# 13_FLOW_Sensor.net
KiCad netlist of a schematic drawn in Altium Designer
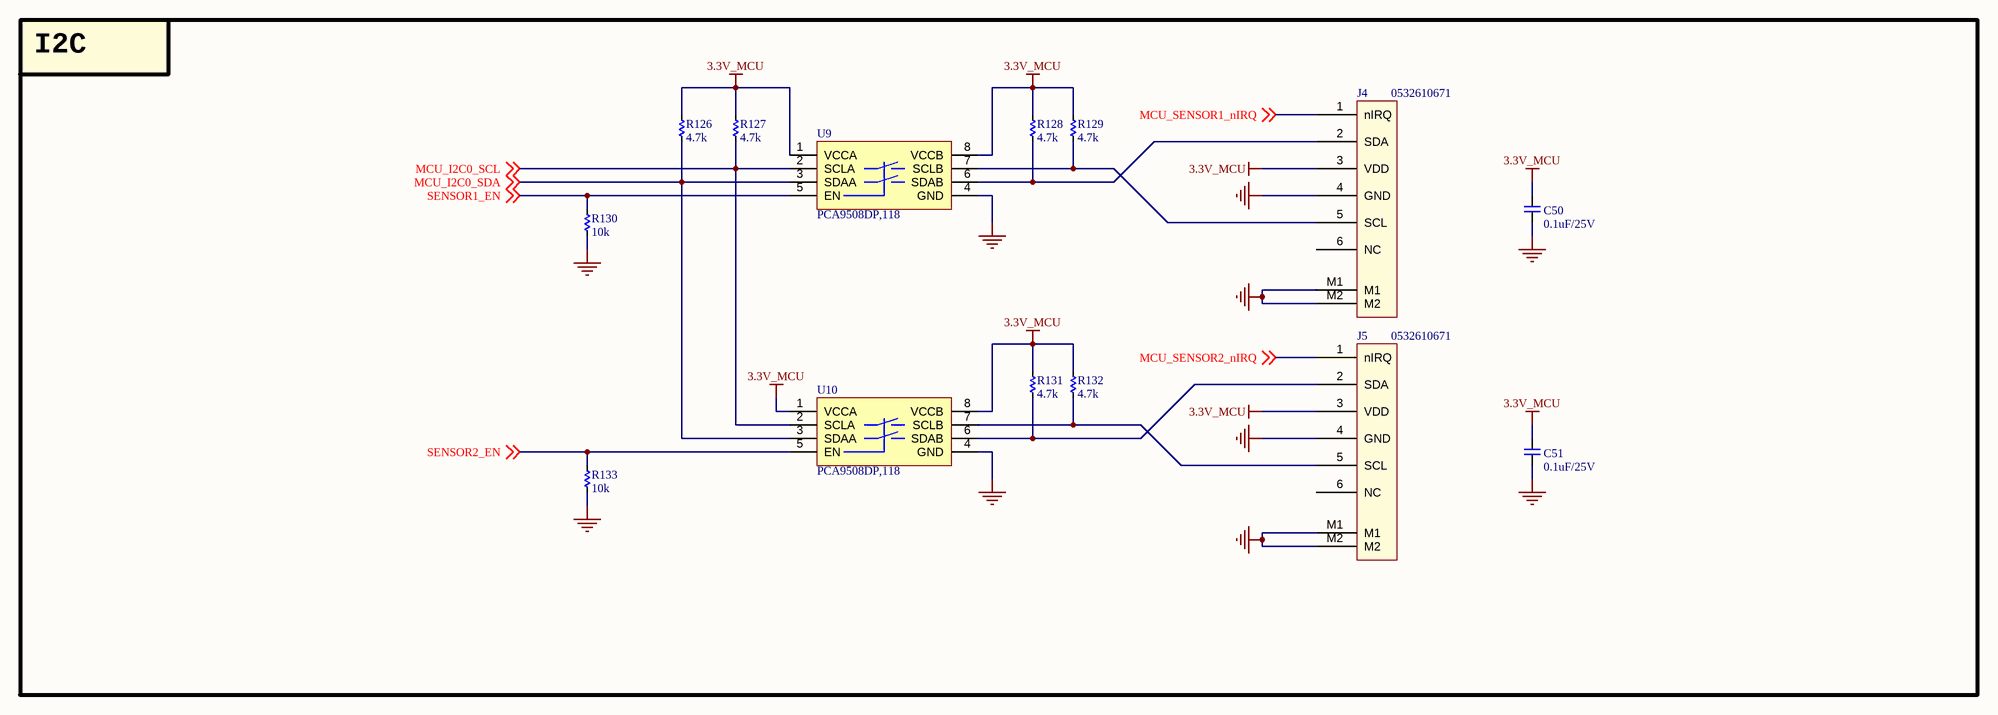
[diagram p0: 13_FLOW_Sensor.SchDoc]

(export (version "E")
  (design (tool "Eeschema 10.0.6"))
  (components
    (comp (ref "C50")
      (value "0.1uF/25V")
      (footprint "CAP_C_1005X60")
      (description "CAP")
      (libsource (lib "LABLIB") (part "_CAP_C_2"))
    )
    (comp (ref "C51")
      (value "0.1uF/25V")
      (footprint "CAP_C_1005X60")
      (description "CAP")
      (libsource (lib "LABLIB") (part "_CAP_C_2"))
    )
    (comp (ref "J4")
      (value "0532610671")
      (footprint "MOLEX_0532610671")
      (libsource (lib "LABLIB") (part "FLOW_SENSOR"))
    )
    (comp (ref "J5")
      (value "0532610671")
      (footprint "MOLEX_0532610671")
      (libsource (lib "LABLIB") (part "FLOW_SENSOR"))
    )
    (comp (ref "R126")
      (value "4.7k")
      (footprint "RES_C_1005X40")
      (description "RES")
      (libsource (lib "LABLIB") (part "_RES_B_2"))
    )
    (comp (ref "R127")
      (value "4.7k")
      (footprint "RES_C_1005X40")
      (description "RES")
      (libsource (lib "LABLIB") (part "_RES_B_2"))
    )
    (comp (ref "R128")
      (value "4.7k")
      (footprint "RES_C_1005X40")
      (description "RES")
      (libsource (lib "LABLIB") (part "_RES_B_2"))
    )
    (comp (ref "R129")
      (value "4.7k")
      (footprint "RES_C_1005X40")
      (description "RES")
      (libsource (lib "LABLIB") (part "_RES_B_2"))
    )
    (comp (ref "R130")
      (value "10k")
      (footprint "RES_C_1005X40")
      (description "RES")
      (libsource (lib "LABLIB") (part "_RES_B_2"))
    )
    (comp (ref "R131")
      (value "4.7k")
      (footprint "RES_C_1005X40")
      (description "RES")
      (libsource (lib "LABLIB") (part "_RES_B_2"))
    )
    (comp (ref "R132")
      (value "4.7k")
      (footprint "RES_C_1005X40")
      (description "RES")
      (libsource (lib "LABLIB") (part "_RES_B_2"))
    )
    (comp (ref "R133")
      (value "10k")
      (footprint "RES_C_1005X40")
      (description "RES")
      (libsource (lib "LABLIB") (part "_RES_B_2"))
    )
    (comp (ref "U9")
      (value "PCA9508DP,118")
      (footprint "TSOP8")
      (libsource (lib "BEE-DAL_EXP_sche") (part "PCA9508DP,118"))
    )
    (comp (ref "U10")
      (value "PCA9508DP,118")
      (footprint "TSOP8")
      (libsource (lib "BEE-DAL_EXP_sche") (part "PCA9508DP,118"))
    )
  )
  (nets
    (net (code "1") (name "3.3V_MCU") (class "Default")
      (node (ref "C50") (pin "2") (pinfunction "2_2") (pintype "passive"))
      (node (ref "C51") (pin "2") (pinfunction "2_2") (pintype "passive"))
      (node (ref "J4") (pin "3") (pinfunction "VDD_3") (pintype "passive"))
      (node (ref "J5") (pin "3") (pinfunction "VDD_3") (pintype "passive"))
      (node (ref "R126") (pin "1") (pinfunction "1_1") (pintype "passive"))
      (node (ref "R127") (pin "1") (pinfunction "1_1") (pintype "passive"))
      (node (ref "R128") (pin "1") (pinfunction "1_1") (pintype "passive"))
      (node (ref "R129") (pin "1") (pinfunction "1_1") (pintype "passive"))
      (node (ref "R131") (pin "1") (pinfunction "1_1") (pintype "passive"))
      (node (ref "R132") (pin "1") (pinfunction "1_1") (pintype "passive"))
      (node (ref "U10") (pin "1") (pinfunction "VCCA_1") (pintype "passive"))
      (node (ref "U10") (pin "8") (pinfunction "VCCB_8") (pintype "passive"))
      (node (ref "U9") (pin "1") (pinfunction "VCCA_1") (pintype "passive"))
      (node (ref "U9") (pin "8") (pinfunction "VCCB_8") (pintype "passive"))
    )
    (net (code "2") (name "GND") (class "Default")
      (node (ref "C50") (pin "1") (pinfunction "1_1") (pintype "passive"))
      (node (ref "C51") (pin "1") (pinfunction "1_1") (pintype "passive"))
      (node (ref "J4") (pin "4") (pinfunction "GND_4") (pintype "passive"))
      (node (ref "J4") (pin "M1") (pinfunction "M1_M1") (pintype "passive"))
      (node (ref "J4") (pin "M2") (pinfunction "M2_M2") (pintype "passive"))
      (node (ref "J5") (pin "4") (pinfunction "GND_4") (pintype "passive"))
      (node (ref "J5") (pin "M1") (pinfunction "M1_M1") (pintype "passive"))
      (node (ref "J5") (pin "M2") (pinfunction "M2_M2") (pintype "passive"))
      (node (ref "R130") (pin "2") (pinfunction "2_2") (pintype "passive"))
      (node (ref "R133") (pin "2") (pinfunction "2_2") (pintype "passive"))
      (node (ref "U10") (pin "4") (pinfunction "GND_4") (pintype "passive"))
      (node (ref "U9") (pin "4") (pinfunction "GND_4") (pintype "passive"))
    )
    (net (code "3") (name "MCU_I2C0_SCL") (class "Default")
      (node (ref "R127") (pin "2") (pinfunction "2_2") (pintype "passive"))
      (node (ref "U10") (pin "2") (pinfunction "SCLA_2") (pintype "passive"))
      (node (ref "U9") (pin "2") (pinfunction "SCLA_2") (pintype "passive"))
    )
    (net (code "4") (name "MCU_I2C0_SDA") (class "Default")
      (node (ref "R126") (pin "2") (pinfunction "2_2") (pintype "passive"))
      (node (ref "U10") (pin "3") (pinfunction "SDAA_3") (pintype "passive"))
      (node (ref "U9") (pin "3") (pinfunction "SDAA_3") (pintype "passive"))
    )
    (net (code "5") (name "MCU_SENSOR1_nIRQ") (class "Default")
      (node (ref "J4") (pin "1") (pinfunction "nIRQ_1") (pintype "passive"))
    )
    (net (code "6") (name "MCU_SENSOR2_nIRQ") (class "Default")
      (node (ref "J5") (pin "1") (pinfunction "nIRQ_1") (pintype "passive"))
    )
    (net (code "7") (name "Net-(J4-SCL)") (class "Default")
      (node (ref "J4") (pin "5") (pinfunction "SCL_5") (pintype "passive"))
      (node (ref "R129") (pin "2") (pinfunction "2_2") (pintype "passive"))
      (node (ref "U9") (pin "7") (pinfunction "SCLB_7") (pintype "passive"))
    )
    (net (code "8") (name "Net-(J4-SDA)") (class "Default")
      (node (ref "J4") (pin "2") (pinfunction "SDA_2") (pintype "passive"))
      (node (ref "R128") (pin "2") (pinfunction "2_2") (pintype "passive"))
      (node (ref "U9") (pin "6") (pinfunction "SDAB_6") (pintype "passive"))
    )
    (net (code "9") (name "Net-(J5-SCL)") (class "Default")
      (node (ref "J5") (pin "5") (pinfunction "SCL_5") (pintype "passive"))
      (node (ref "R132") (pin "2") (pinfunction "2_2") (pintype "passive"))
      (node (ref "U10") (pin "7") (pinfunction "SCLB_7") (pintype "passive"))
    )
    (net (code "10") (name "Net-(J5-SDA)") (class "Default")
      (node (ref "J5") (pin "2") (pinfunction "SDA_2") (pintype "passive"))
      (node (ref "R131") (pin "2") (pinfunction "2_2") (pintype "passive"))
      (node (ref "U10") (pin "6") (pinfunction "SDAB_6") (pintype "passive"))
    )
    (net (code "11") (name "SENSOR1_EN") (class "Default")
      (node (ref "R130") (pin "1") (pinfunction "1_1") (pintype "passive"))
      (node (ref "U9") (pin "5") (pinfunction "EN_5") (pintype "passive"))
    )
    (net (code "12") (name "SENSOR2_EN") (class "Default")
      (node (ref "R133") (pin "1") (pinfunction "1_1") (pintype "passive"))
      (node (ref "U10") (pin "5") (pinfunction "EN_5") (pintype "passive"))
    )
    (net (code "13") (name "unconnected-(J4-NC-Pad6)") (class "Default")
      (node (ref "J4") (pin "6") (pinfunction "NC_6") (pintype "passive"))
    )
    (net (code "14") (name "unconnected-(J5-NC-Pad6)") (class "Default")
      (node (ref "J5") (pin "6") (pinfunction "NC_6") (pintype "passive"))
    )
  )
)
